# HeaterController.net
KiCad netlist of a schematic drawn in Altium Designer
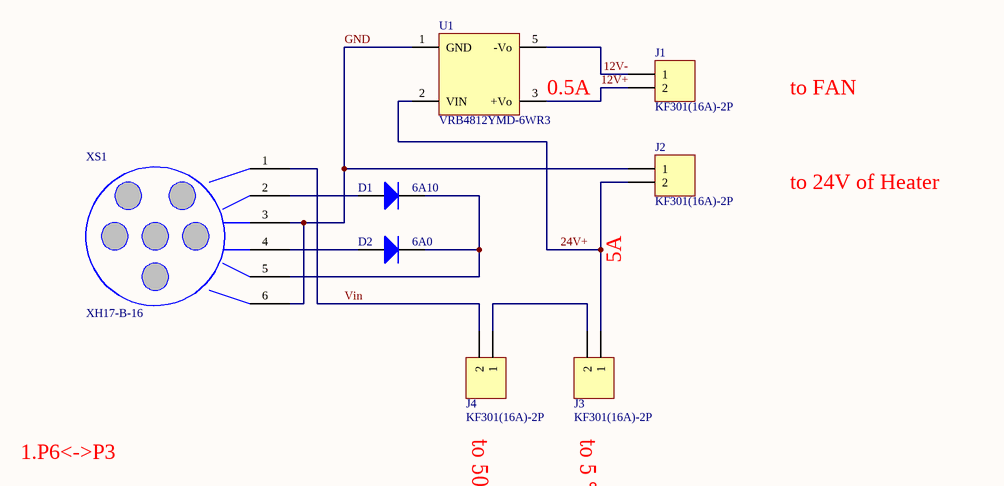
[diagram p0: HeaterController.SchDoc]

(export (version "E")
  (design (tool "Eeschema 10.0.6"))
  (components
    (comp (ref "D1")
      (value "6A10")
      (footprint "P600(R-6)")
      (description "Default Diode")
      (fields (field (name "PUBLISHER") "Altium Limited"))
      (libsource (lib "Miscellaneous Devices") (part "Diode"))
    )
    (comp (ref "D2")
      (value "6A0")
      (footprint "P600(r-6)")
      (description "Default Diode")
      (fields (field (name "PUBLISHER") "Altium Limited"))
      (libsource (lib "Miscellaneous Devices") (part "Diode"))
    )
    (comp (ref "J1")
      (value "KF301(16A)-2P")
      (footprint "KF301(16A)-2P")
      (description "Header, 2-Pin")
      (fields (field (name "PUBLISHER") "Altium Limited"))
      (libsource (lib "") (part "Header 2_1"))
    )
    (comp (ref "J2")
      (value "KF301(16A)-2P")
      (footprint "KF301(16A)-2P")
      (description "Header, 2-Pin")
      (fields (field (name "PUBLISHER") "Altium Limited"))
      (libsource (lib "") (part "Header 2_1"))
    )
    (comp (ref "J3")
      (value "KF301(16A)-2P")
      (footprint "KF301(16A)-2P")
      (description "Header, 2-Pin")
      (fields (field (name "PUBLISHER") "Altium Limited"))
      (libsource (lib "Miscellaneous Connectors") (part "Header 2"))
    )
    (comp (ref "J4")
      (value "KF301(16A)-2P")
      (footprint "KF301(16A)-2P")
      (description "Header, 2-Pin")
      (fields (field (name "PUBLISHER") "Altium Limited"))
      (libsource (lib "Miscellaneous Connectors") (part "Header 2"))
    )
    (comp (ref "U1")
      (value "VRB4812YMD-6WR3")
      (footprint "VRB_YMD-6WR3")
      (libsource (lib "HeaterController") (part "VRB_YMD-6WR3"))
    )
    (comp (ref "XS1")
      (value "XH17-B-16")
      (footprint "XH17-B-16")
      (libsource (lib "HeaterController") (part "XH17-B-16"))
    )
  )
  (nets
    (net (code "1") (name "/12V+") (class "Default")
      (node (ref "J1") (pin "2") (pinfunction "2_2") (pintype "passive"))
      (node (ref "U1") (pin "3") (pinfunction "+Vo_3") (pintype "passive"))
    )
    (net (code "2") (name "/12V-") (class "Default")
      (node (ref "J1") (pin "1") (pinfunction "1_1") (pintype "passive"))
      (node (ref "U1") (pin "5") (pinfunction "-Vo_5") (pintype "passive"))
    )
    (net (code "3") (name "/24V+") (class "Default")
      (node (ref "J2") (pin "2") (pinfunction "2_2") (pintype "passive"))
      (node (ref "J3") (pin "1") (pinfunction "1_1") (pintype "passive"))
      (node (ref "U1") (pin "2") (pinfunction "VIN_2") (pintype "passive"))
    )
    (net (code "4") (name "/GND") (class "Default")
      (node (ref "J2") (pin "1") (pinfunction "1_1") (pintype "passive"))
      (node (ref "U1") (pin "1") (pinfunction "GND_1") (pintype "passive"))
      (node (ref "XS1") (pin "3") (pinfunction "3_3") (pintype "passive"))
      (node (ref "XS1") (pin "6") (pinfunction "6_6") (pintype "passive"))
    )
    (net (code "5") (name "/Vin") (class "Default")
      (node (ref "J4") (pin "2") (pinfunction "2_2") (pintype "passive"))
      (node (ref "XS1") (pin "1") (pinfunction "1_1") (pintype "passive"))
    )
    (net (code "6") (name "Net-(D1-A)") (class "Default")
      (node (ref "D1") (pin "1") (pinfunction "A_1") (pintype "passive"))
      (node (ref "XS1") (pin "2") (pinfunction "2_2") (pintype "passive"))
    )
    (net (code "7") (name "Net-(D1-K)") (class "Default")
      (node (ref "D1") (pin "2") (pinfunction "K_2") (pintype "passive"))
      (node (ref "D2") (pin "2") (pinfunction "K_2") (pintype "passive"))
      (node (ref "XS1") (pin "5") (pinfunction "5_5") (pintype "passive"))
    )
    (net (code "8") (name "Net-(D2-A)") (class "Default")
      (node (ref "D2") (pin "1") (pinfunction "A_1") (pintype "passive"))
      (node (ref "XS1") (pin "4") (pinfunction "4_4") (pintype "passive"))
    )
    (net (code "9") (name "Net-(J3-Pad2)") (class "Default")
      (node (ref "J3") (pin "2") (pinfunction "2_2") (pintype "passive"))
      (node (ref "J4") (pin "1") (pinfunction "1_1") (pintype "passive"))
    )
  )
)
